# IPMC_MACP_-_2.net
KiCad netlist of a schematic drawn in Altium Designer
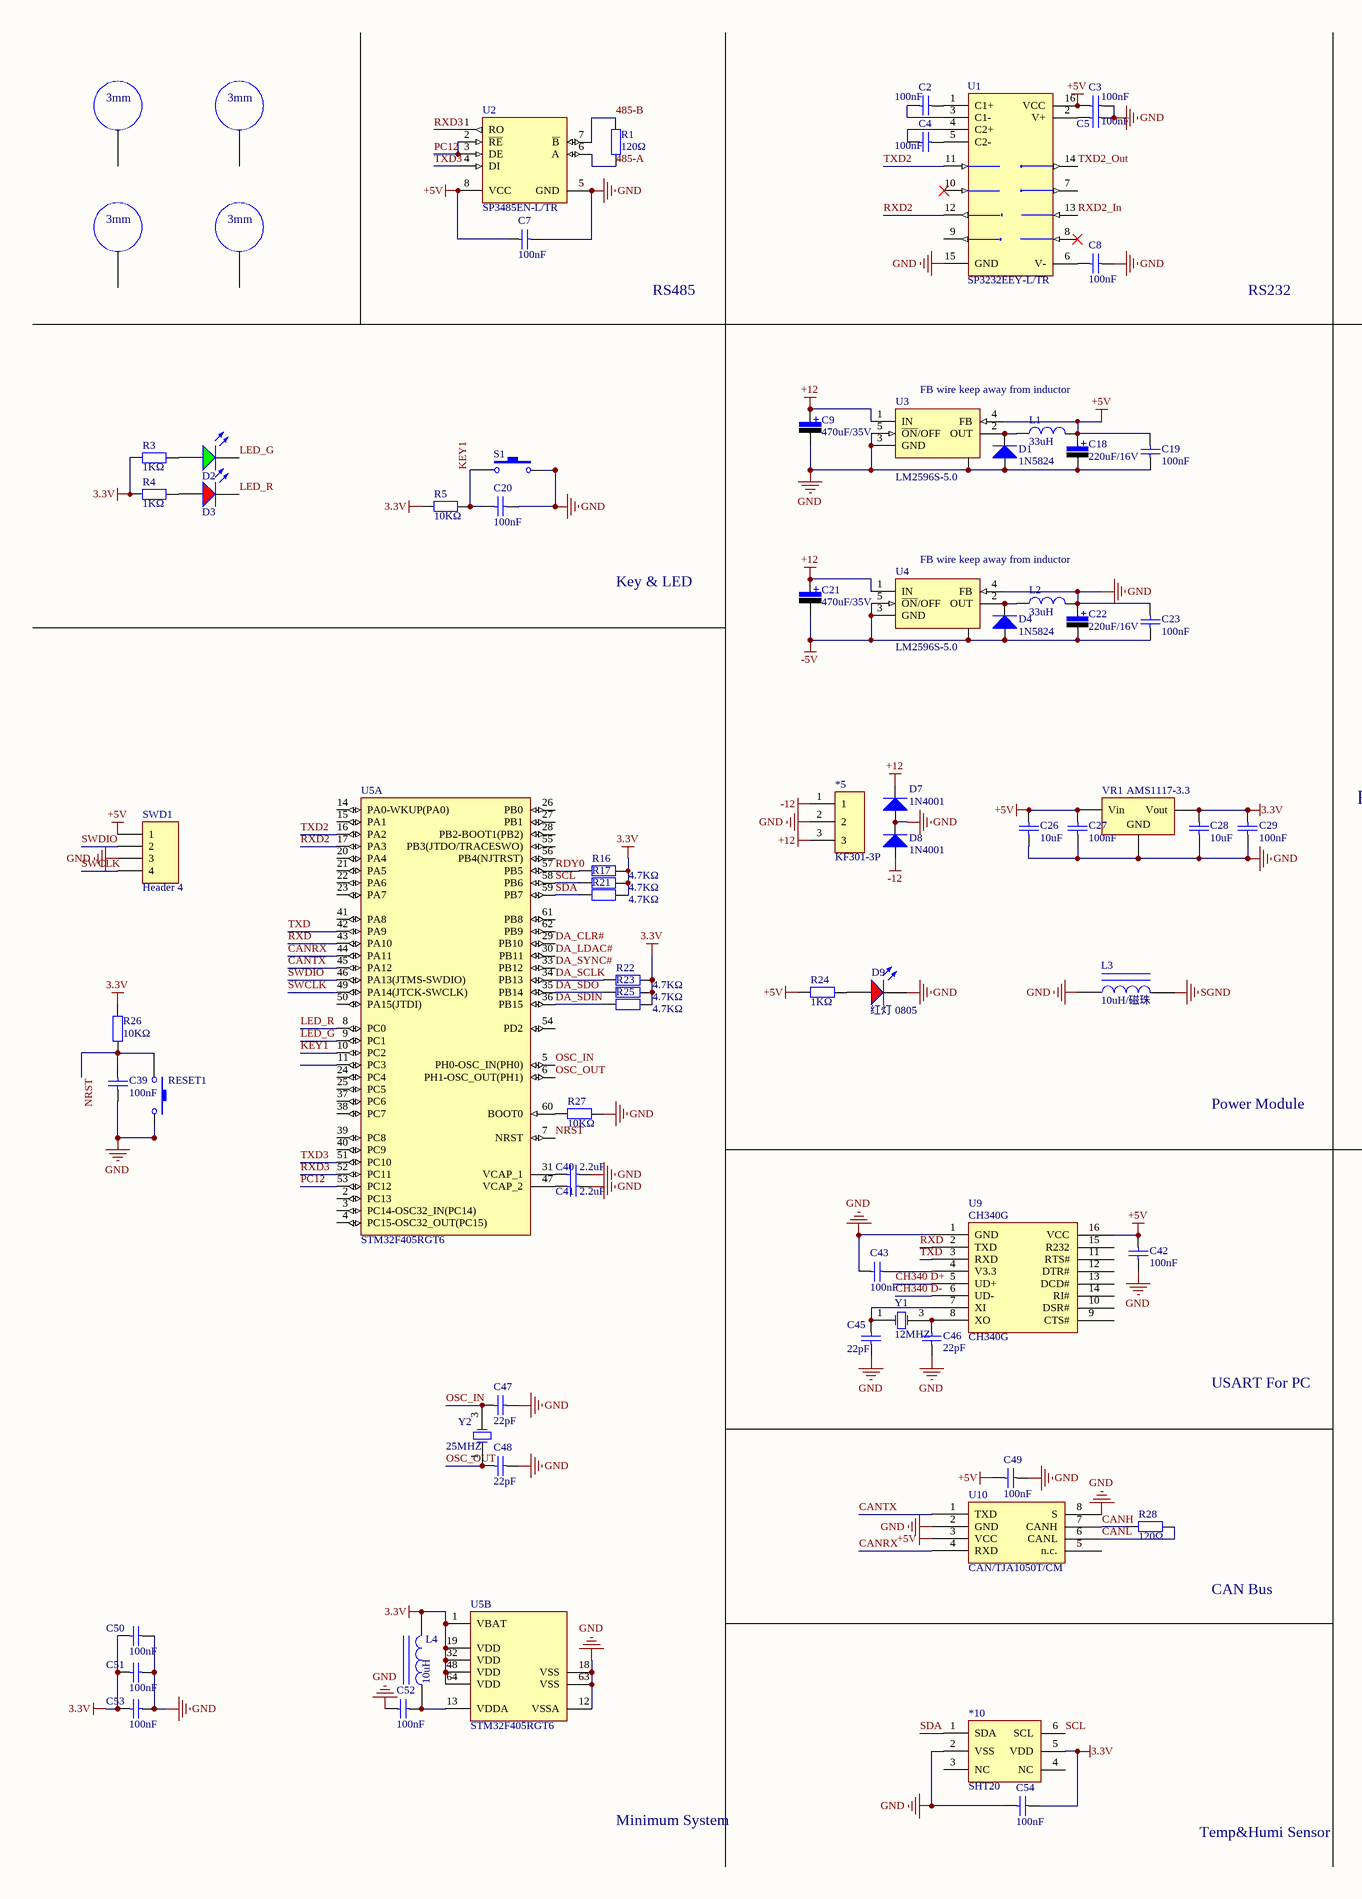
[diagram p0: IPMC_MACP - 完成2.SchDoc, left]
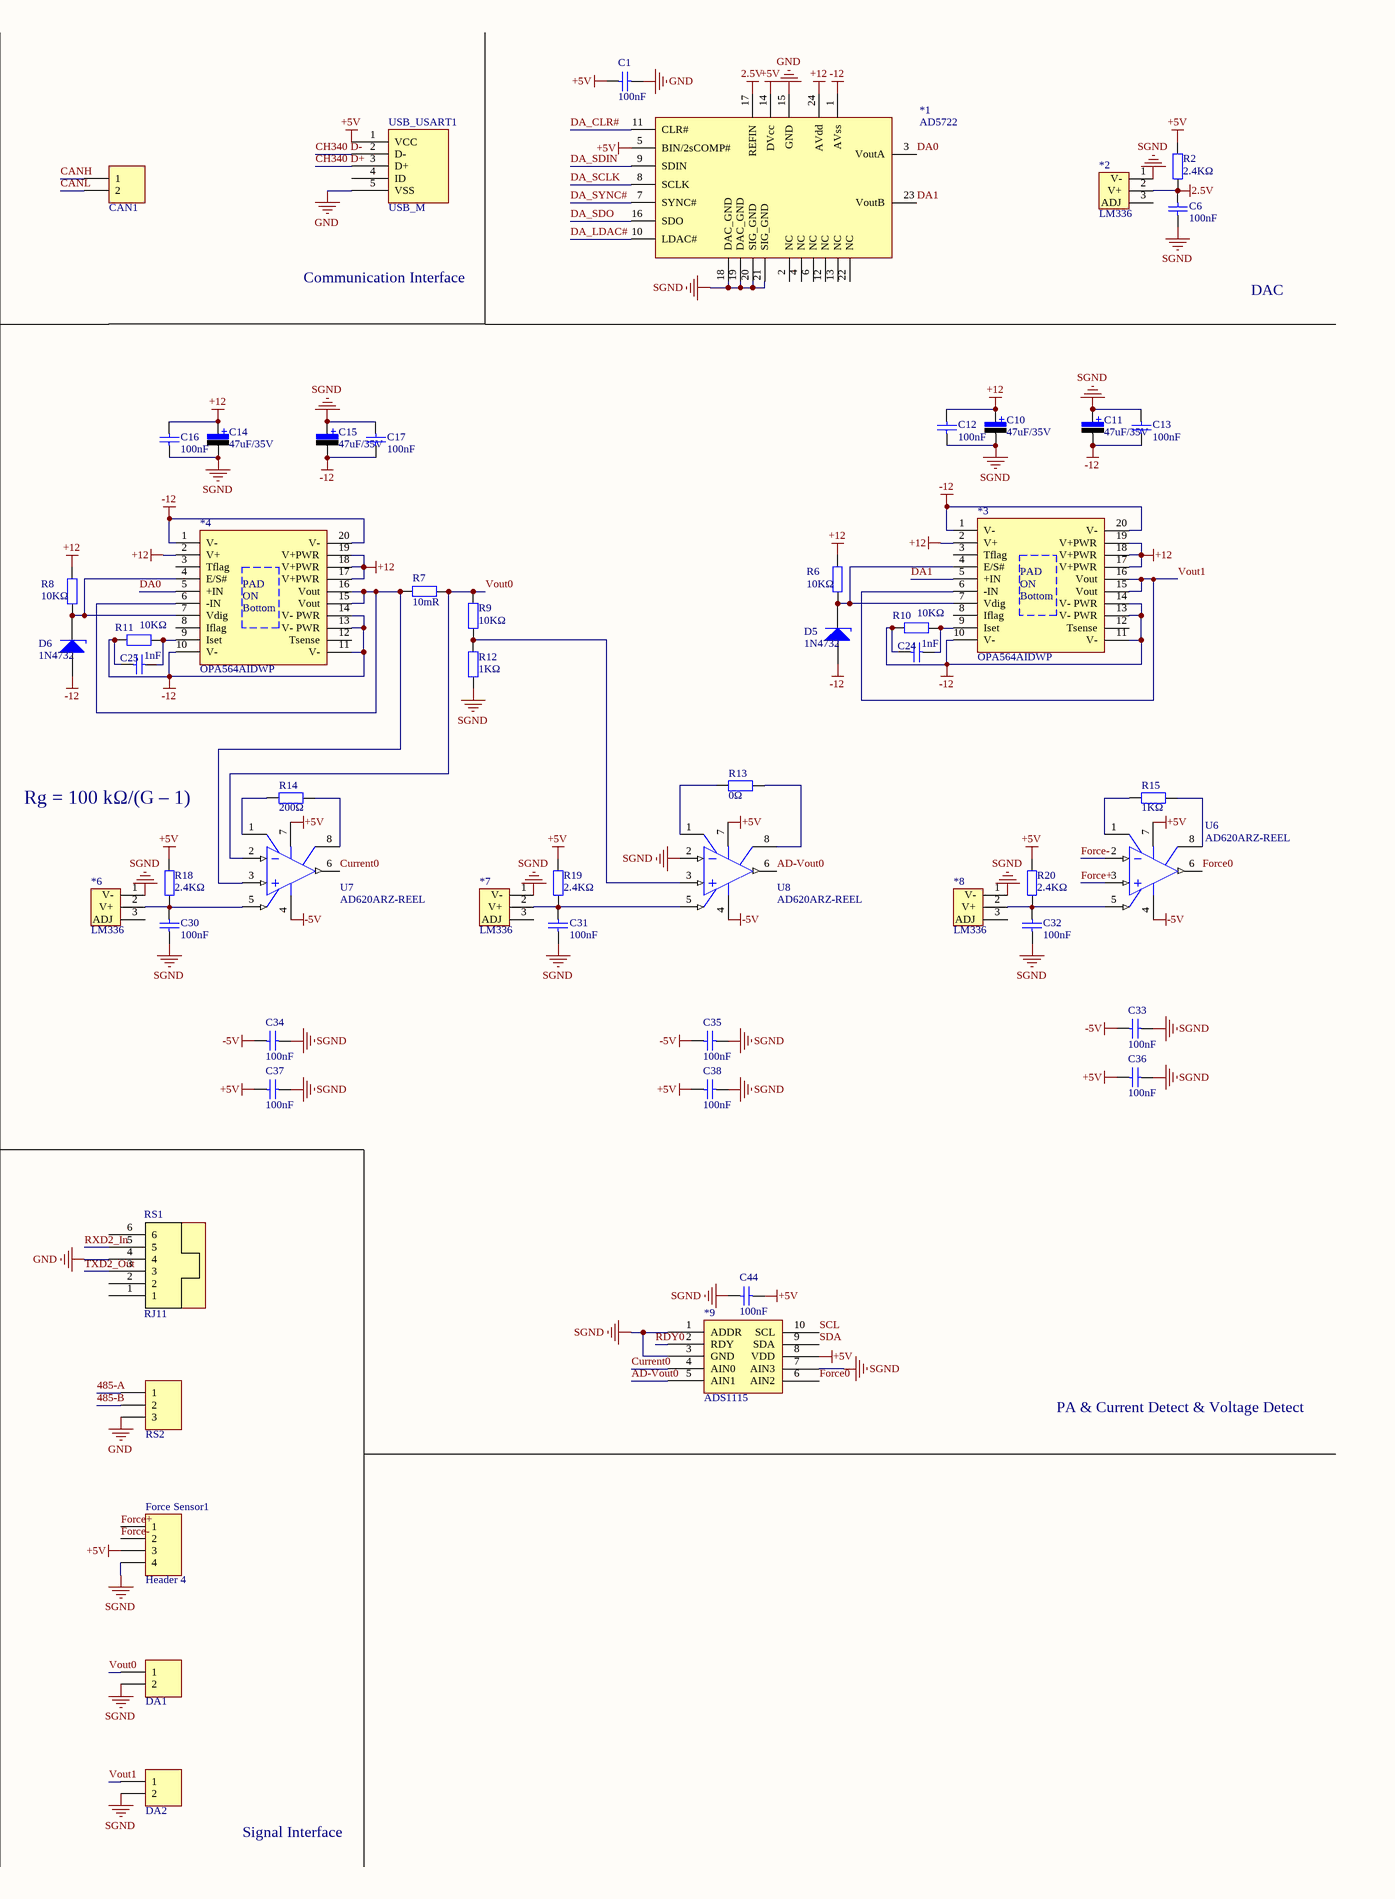
[diagram p1: IPMC_MACP - 完成2.SchDoc, right]

(export (version "E")
  (design (tool "Eeschema 10.0.6"))
  (components
    (comp (ref "*1")
      (value "AD5722")
      (footprint "TSSOP24P")
      (description "双极性DAC")
      (libsource (lib "fszhang") (part "AD5722"))
    )
    (comp (ref "*2")
      (value "LM336")
      (footprint "TO-92A")
      (description "基准电压芯片2.5/5V")
      (libsource (lib "fszhang") (part "LM336"))
    )
    (comp (ref "*3")
      (value "OPA564AIDWP")
      (footprint "HSOP20")
      (description "PAD on Bottom")
      (libsource (lib "fszhang") (part "OPA564AIDWP"))
    )
    (comp (ref "*4")
      (value "OPA564AIDWP")
      (footprint "HSOP20")
      (description "PAD on Bottom")
      (libsource (lib "fszhang") (part "OPA564AIDWP"))
    )
    (comp (ref "*5")
      (value "KF301-3P")
      (footprint "KF301-3P")
      (description "蓝色端子")
      (libsource (lib "fszhang") (part "KF301-3P"))
    )
    (comp (ref "*6")
      (value "LM336")
      (footprint "TO-92A")
      (description "基准电压芯片2.5/5V")
      (libsource (lib "fszhang") (part "LM336"))
    )
    (comp (ref "*7")
      (value "LM336")
      (footprint "TO-92A")
      (description "基准电压芯片2.5/5V")
      (libsource (lib "fszhang") (part "LM336"))
    )
    (comp (ref "*8")
      (value "LM336")
      (footprint "TO-92A")
      (description "基准电压芯片2.5/5V")
      (libsource (lib "fszhang") (part "LM336"))
    )
    (comp (ref "*9") (value "ADS1115") (footprint "MSOP-UN10_N") (libsource (lib "fszhang") (part "ADS1115")))
    (comp (ref "*10") (value "SHT20") (footprint "DFN6") (libsource (lib "fszhang") (part "SHT20")))
    (comp (ref "C1")
      (value "100nF")
      (footprint "0805_C")
      (description "贴片电容")
      (libsource (lib "Miscellaneous Devices LC") (part "0805 100nF(104) 10% 50V"))
    )
    (comp (ref "C2")
      (value "100nF")
      (footprint "0805_C")
      (description "贴片电容")
      (libsource (lib "Miscellaneous Devices LC") (part "0805 100nF(104) 10% 50V"))
    )
    (comp (ref "C3")
      (value "100nF")
      (footprint "0805_C")
      (description "贴片电容")
      (libsource (lib "Miscellaneous Devices LC") (part "0805 100nF(104) 10% 50V"))
    )
    (comp (ref "C4")
      (value "100nF")
      (footprint "0805_C")
      (description "贴片电容")
      (libsource (lib "Miscellaneous Devices LC") (part "0805 100nF(104) 10% 50V"))
    )
    (comp (ref "C5")
      (value "100nF")
      (footprint "0805_C")
      (description "贴片电容")
      (libsource (lib "Miscellaneous Devices LC") (part "0805 100nF(104) 10% 50V"))
    )
    (comp (ref "C6")
      (value "100nF")
      (footprint "0805_C")
      (description "贴片电容")
      (libsource (lib "Miscellaneous Devices LC") (part "0805 100nF(104) 10% 50V"))
    )
    (comp (ref "C7")
      (value "100nF")
      (footprint "0805_C")
      (description "贴片电容")
      (libsource (lib "Miscellaneous Devices LC") (part "0805 100nF(104) 10% 50V"))
    )
    (comp (ref "C8")
      (value "100nF")
      (footprint "0805_C")
      (description "贴片电容")
      (libsource (lib "Miscellaneous Devices LC") (part "0805 100nF(104) 10% 50V"))
    )
    (comp (ref "C9")
      (value "470uF/35V")
      (footprint "C-RB-S10")
      (description "极性电解电容")
      (fields (field (name "PUBLISHER") "Altium Limited"))
      (libsource (lib "fszhang") (part "Cap Pol"))
    )
    (comp (ref "C10")
      (value "47uF/35V")
      (footprint "C-RB-S6")
      (description "极性电解电容")
      (fields (field (name "PUBLISHER") "Altium Limited"))
      (libsource (lib "fszhang") (part "Cap Pol"))
    )
    (comp (ref "C11")
      (value "47uF/35V")
      (footprint "C-RB-S6")
      (description "极性电解电容")
      (fields (field (name "PUBLISHER") "Altium Limited"))
      (libsource (lib "fszhang") (part "Cap Pol"))
    )
    (comp (ref "C12")
      (value "100nF")
      (footprint "0805_C")
      (description "贴片电容")
      (libsource (lib "Miscellaneous Devices LC") (part "0805 100nF(104) 10% 50V"))
    )
    (comp (ref "C13")
      (value "100nF")
      (footprint "0805_C")
      (description "贴片电容")
      (libsource (lib "Miscellaneous Devices LC") (part "0805 100nF(104) 10% 50V"))
    )
    (comp (ref "C14")
      (value "47uF/35V")
      (footprint "C-RB-S6")
      (description "极性电解电容")
      (fields (field (name "PUBLISHER") "Altium Limited"))
      (libsource (lib "fszhang") (part "Cap Pol"))
    )
    (comp (ref "C15")
      (value "47uF/35V")
      (footprint "C-RB-S6")
      (description "极性电解电容")
      (fields (field (name "PUBLISHER") "Altium Limited"))
      (libsource (lib "fszhang") (part "Cap Pol"))
    )
    (comp (ref "C16")
      (value "100nF")
      (footprint "0805_C")
      (description "贴片电容")
      (libsource (lib "Miscellaneous Devices LC") (part "0805 100nF(104) 10% 50V"))
    )
    (comp (ref "C17")
      (value "100nF")
      (footprint "0805_C")
      (description "贴片电容")
      (libsource (lib "Miscellaneous Devices LC") (part "0805 100nF(104) 10% 50V"))
    )
    (comp (ref "C18")
      (value "220uF/16V")
      (footprint "C-RB-S6")
      (description "极性电解电容")
      (fields (field (name "PUBLISHER") "Altium Limited"))
      (libsource (lib "fszhang") (part "Cap Pol"))
    )
    (comp (ref "C19")
      (value "100nF")
      (footprint "0805_C")
      (description "贴片电容")
      (libsource (lib "Miscellaneous Devices LC") (part "0805 100nF(104) 10% 50V"))
    )
    (comp (ref "C20")
      (value "100nF")
      (footprint "0805_C")
      (description "贴片电容")
      (libsource (lib "Miscellaneous Devices LC") (part "0805 100nF(104) 10% 50V"))
    )
    (comp (ref "C21")
      (value "470uF/35V")
      (footprint "C-RB-S10")
      (description "极性电解电容")
      (fields (field (name "PUBLISHER") "Altium Limited"))
      (libsource (lib "fszhang") (part "Cap Pol"))
    )
    (comp (ref "C22")
      (value "220uF/16V")
      (footprint "C-RB-S6")
      (description "极性电解电容")
      (fields (field (name "PUBLISHER") "Altium Limited"))
      (libsource (lib "fszhang") (part "Cap Pol"))
    )
    (comp (ref "C23")
      (value "100nF")
      (footprint "0805_C")
      (description "贴片电容")
      (libsource (lib "Miscellaneous Devices LC") (part "0805 100nF(104) 10% 50V"))
    )
    (comp (ref "C24")
      (value "1nF")
      (footprint "0805_C")
      (description "贴片电容")
      (libsource (lib "Miscellaneous Devices LC") (part "0805 1nF (102) 10% 50V"))
    )
    (comp (ref "C25")
      (value "1nF")
      (footprint "0805_C")
      (description "贴片电容")
      (libsource (lib "Miscellaneous Devices LC") (part "0805 1nF (102) 10% 50V"))
    )
    (comp (ref "C26")
      (value "10uF")
      (footprint "0805_C")
      (description "贴片电容")
      (libsource (lib "Miscellaneous Devices LC") (part "0805 10uF (106) 10% 25V"))
    )
    (comp (ref "C27")
      (value "100nF")
      (footprint "0805_C")
      (description "贴片电容")
      (libsource (lib "Miscellaneous Devices LC") (part "0805 100nF(104) 10% 50V"))
    )
    (comp (ref "C28")
      (value "10uF")
      (footprint "0805_C")
      (description "贴片电容")
      (libsource (lib "Miscellaneous Devices LC") (part "0805 10uF (106) 10% 25V"))
    )
    (comp (ref "C29")
      (value "100nF")
      (footprint "0805_C")
      (description "贴片电容")
      (libsource (lib "Miscellaneous Devices LC") (part "0805 100nF(104) 10% 50V"))
    )
    (comp (ref "C30")
      (value "100nF")
      (footprint "0805_C")
      (description "贴片电容")
      (libsource (lib "Miscellaneous Devices LC") (part "0805 100nF(104) 10% 50V"))
    )
    (comp (ref "C31")
      (value "100nF")
      (footprint "0805_C")
      (description "贴片电容")
      (libsource (lib "Miscellaneous Devices LC") (part "0805 100nF(104) 10% 50V"))
    )
    (comp (ref "C32")
      (value "100nF")
      (footprint "0805_C")
      (description "贴片电容")
      (libsource (lib "Miscellaneous Devices LC") (part "0805 100nF(104) 10% 50V"))
    )
    (comp (ref "C33")
      (value "100nF")
      (footprint "0805_C")
      (description "贴片电容")
      (libsource (lib "Miscellaneous Devices LC") (part "0805 100nF(104) 10% 50V"))
    )
    (comp (ref "C34")
      (value "100nF")
      (footprint "0805_C")
      (description "贴片电容")
      (libsource (lib "Miscellaneous Devices LC") (part "0805 100nF(104) 10% 50V"))
    )
    (comp (ref "C35")
      (value "100nF")
      (footprint "0805_C")
      (description "贴片电容")
      (libsource (lib "Miscellaneous Devices LC") (part "0805 100nF(104) 10% 50V"))
    )
    (comp (ref "C36")
      (value "100nF")
      (footprint "0805_C")
      (description "贴片电容")
      (libsource (lib "Miscellaneous Devices LC") (part "0805 100nF(104) 10% 50V"))
    )
    (comp (ref "C37")
      (value "100nF")
      (footprint "0805_C")
      (description "贴片电容")
      (libsource (lib "Miscellaneous Devices LC") (part "0805 100nF(104) 10% 50V"))
    )
    (comp (ref "C38")
      (value "100nF")
      (footprint "0805_C")
      (description "贴片电容")
      (libsource (lib "Miscellaneous Devices LC") (part "0805 100nF(104) 10% 50V"))
    )
    (comp (ref "C39")
      (value "100nF")
      (footprint "0805_C")
      (description "贴片电容")
      (libsource (lib "Miscellaneous Devices LC") (part "0805 100nF(104) 10% 50V"))
    )
    (comp (ref "C40")
      (value "2.2uF")
      (footprint "0805_C")
      (description "贴片电容")
      (libsource (lib "Miscellaneous Devices LC") (part "0805 2.2uF (225) 20% 50V"))
    )
    (comp (ref "C41")
      (value "2.2uF")
      (footprint "0805_C")
      (description "贴片电容")
      (libsource (lib "Miscellaneous Devices LC") (part "0805 2.2uF (225) 20% 50V"))
    )
    (comp (ref "C42")
      (value "100nF")
      (footprint "0805_C")
      (description "贴片电容")
      (libsource (lib "Miscellaneous Devices LC") (part "0805 100nF(104) 10% 50V"))
    )
    (comp (ref "C43")
      (value "100nF")
      (footprint "0805_C")
      (description "贴片电容")
      (libsource (lib "Miscellaneous Devices LC") (part "0805 100nF(104) 10% 50V"))
    )
    (comp (ref "C44")
      (value "100nF")
      (footprint "0805_C")
      (description "贴片电容")
      (libsource (lib "Miscellaneous Devices LC") (part "0805 100nF(104) 10% 50V"))
    )
    (comp (ref "C45")
      (value "22pF")
      (footprint "0805_C")
      (description "贴片电容")
      (libsource (lib "Miscellaneous Devices LC") (part "0805 22pF (220) 5% 50V"))
    )
    (comp (ref "C46")
      (value "22pF")
      (footprint "0805_C")
      (description "贴片电容")
      (libsource (lib "Miscellaneous Devices LC") (part "0805 22pF (220) 5% 50V"))
    )
    (comp (ref "C47")
      (value "22pF")
      (footprint "0805_C")
      (description "贴片电容")
      (libsource (lib "Miscellaneous Devices LC") (part "0805 22pF (220) 5% 50V"))
    )
    (comp (ref "C48")
      (value "22pF")
      (footprint "0805_C")
      (description "贴片电容")
      (libsource (lib "Miscellaneous Devices LC") (part "0805 22pF (220) 5% 50V"))
    )
    (comp (ref "C49")
      (value "100nF")
      (footprint "0805_C")
      (description "贴片电容")
      (libsource (lib "Miscellaneous Devices LC") (part "0805 100nF(104) 10% 50V"))
    )
    (comp (ref "C50")
      (value "100nF")
      (footprint "0805_C")
      (description "贴片电容")
      (libsource (lib "Miscellaneous Devices LC") (part "0805 100nF(104) 10% 50V"))
    )
    (comp (ref "C51")
      (value "100nF")
      (footprint "0805_C")
      (description "贴片电容")
      (libsource (lib "Miscellaneous Devices LC") (part "0805 100nF(104) 10% 50V"))
    )
    (comp (ref "C52")
      (value "100nF")
      (footprint "0805_C")
      (description "贴片电容")
      (libsource (lib "Miscellaneous Devices LC") (part "0805 100nF(104) 10% 50V"))
    )
    (comp (ref "C53")
      (value "100nF")
      (footprint "0805_C")
      (description "贴片电容")
      (libsource (lib "Miscellaneous Devices LC") (part "0805 100nF(104) 10% 50V"))
    )
    (comp (ref "C54")
      (value "100nF")
      (footprint "0805_C")
      (description "贴片电容")
      (libsource (lib "Miscellaneous Devices LC") (part "0805 100nF(104) 10% 50V"))
    )
    (comp (ref "CAN1")
      (value "Header 2")
      (footprint "HDR2X1_B1")
      (description "接插件")
      (fields (field (name "PUBLISHER") "Altium Limited"))
      (libsource (lib "fszhang") (part "Header 2"))
    )
    (comp (ref "D1")
      (value "1N5824")
      (footprint "DIODE-SMA")
      (description "二极管")
      (fields (field (name "PUBLISHER") "Altium Limited"))
      (libsource (lib "fszhang") (part "Diode"))
    )
    (comp (ref "D2")
      (value "翠绿 0805")
      (footprint "0805_LED_S1")
      (description "发光二极管")
      (libsource (lib "Miscellaneous Devices LC") (part "0805 翠绿"))
    )
    (comp (ref "D3")
      (value "红灯 0805")
      (footprint "0805_LED_S1")
      (description "发光二极管")
      (libsource (lib "Miscellaneous Devices LC") (part "0805 红灯"))
    )
    (comp (ref "D4")
      (value "1N5824")
      (footprint "DIODE-SMA")
      (description "二极管")
      (fields (field (name "PUBLISHER") "Altium Limited"))
      (libsource (lib "fszhang") (part "Diode"))
    )
    (comp (ref "D5")
      (value "1N4732")
      (footprint "DIODE-1206")
      (description "稳压二极管")
      (fields (field (name "PUBLISHER") "Altium Limited"))
      (libsource (lib "fszhang") (part "Diode-Z"))
    )
    (comp (ref "D6")
      (value "1N4732")
      (footprint "DIODE-1206")
      (description "稳压二极管")
      (fields (field (name "PUBLISHER") "Altium Limited"))
      (libsource (lib "fszhang") (part "Diode-Z"))
    )
    (comp (ref "D7")
      (value "1N4001")
      (footprint "DIODE-SMA")
      (description "二极管")
      (fields (field (name "PUBLISHER") "Altium Limited"))
      (libsource (lib "fszhang") (part "Diode"))
    )
    (comp (ref "D8")
      (value "1N4001")
      (footprint "DIODE-SMA")
      (description "二极管")
      (fields (field (name "PUBLISHER") "Altium Limited"))
      (libsource (lib "fszhang") (part "Diode"))
    )
    (comp (ref "D9")
      (value "红灯 0805")
      (footprint "0805_LED_S1")
      (description "发光二极管")
      (libsource (lib "Miscellaneous Devices LC") (part "0805 红灯"))
    )
    (comp (ref "DA1")
      (value "Header 2")
      (footprint "HDR2X1_B1")
      (description "接插件")
      (fields (field (name "PUBLISHER") "Altium Limited"))
      (libsource (lib "fszhang") (part "Header 2"))
    )
    (comp (ref "DA2")
      (value "Header 2")
      (footprint "HDR2X1_B1")
      (description "接插件")
      (fields (field (name "PUBLISHER") "Altium Limited"))
      (libsource (lib "fszhang") (part "Header 2"))
    )
    (comp (ref "Force Sensor1")
      (value "Header 4")
      (footprint "fszhang:HDR4X1_B1")
      (description "Header, 4-Pin")
      (fields (field (name "PUBLISHER") "Altium Limited"))
      (libsource (lib "Miscellaneous Connectors") (part "Header 4"))
    )
    (comp (ref "L1")
      (value "33uH")
      (footprint "L-SMD-12")
      (description "电感")
      (fields (field (name "PUBLISHER") "Altium Limited"))
      (libsource (lib "fszhang") (part "Inductor"))
    )
    (comp (ref "L2")
      (value "33uH")
      (footprint "L-SMD-12")
      (description "电感")
      (fields (field (name "PUBLISHER") "Altium Limited"))
      (libsource (lib "fszhang") (part "Inductor"))
    )
    (comp (ref "L3")
      (value "10uH/磁珠")
      (footprint "0805_L")
      (description "贴片电感")
      (libsource (lib "Miscellaneous Devices LC") (part "0805 10uH 10%"))
    )
    (comp (ref "L4")
      (value "10uH")
      (footprint "0805_L")
      (description "贴片电感")
      (libsource (lib "Miscellaneous Devices LC") (part "0805 10uH 10%"))
    )
    (comp (ref "R1")
      (value "120Ω")
      (footprint "0805_R")
      (description "贴片电阻")
      (libsource (lib "Miscellaneous Devices LC") (part "0805 120Ω (1200) 1%"))
    )
    (comp (ref "R2")
      (value "2.4KΩ")
      (footprint "0805_R")
      (description "贴片电阻")
      (libsource (lib "Miscellaneous Devices LC") (part "0805 2.4KΩ (2401) 1%"))
    )
    (comp (ref "R3")
      (value "1KΩ")
      (footprint "0805_R")
      (description "贴片电阻")
      (libsource (lib "Miscellaneous Devices LC") (part "0805 1KΩ (1001) 1%"))
    )
    (comp (ref "R4")
      (value "1KΩ")
      (footprint "0805_R")
      (description "贴片电阻")
      (libsource (lib "Miscellaneous Devices LC") (part "0805 1KΩ (1001) 1%"))
    )
    (comp (ref "R5")
      (value "10KΩ")
      (footprint "0805_R")
      (description "贴片电阻")
      (libsource (lib "Miscellaneous Devices LC") (part "0805 10KΩ (1002) 1%"))
    )
    (comp (ref "R6")
      (value "10KΩ")
      (footprint "0805_R")
      (description "贴片电阻")
      (libsource (lib "") (part "0805 10KΩ (1002) 1%_2"))
    )
    (comp (ref "R7")
      (value "10mR")
      (footprint "2512")
      (description "贴片电阻")
      (fields (field (name "PUBLISHER") "Altium Limited"))
      (libsource (lib "fszhang") (part "Res1"))
    )
    (comp (ref "R8")
      (value "10KΩ")
      (footprint "0805_R")
      (description "贴片电阻")
      (libsource (lib "") (part "0805 10KΩ (1002) 1%_2"))
    )
    (comp (ref "R9")
      (value "10KΩ")
      (footprint "0805_R")
      (description "贴片电阻")
      (libsource (lib "Miscellaneous Devices LC") (part "0805 20KΩ (2002) 1%"))
    )
    (comp (ref "R10")
      (value "10KΩ")
      (footprint "0805_R")
      (description "贴片电阻")
      (libsource (lib "Miscellaneous Devices LC") (part "0805 10KΩ (1002) 1%"))
    )
    (comp (ref "R11")
      (value "10KΩ")
      (footprint "0805_R")
      (description "贴片电阻")
      (libsource (lib "Miscellaneous Devices LC") (part "0805 10KΩ (1002) 1%"))
    )
    (comp (ref "R12")
      (value "1KΩ")
      (footprint "0805_R")
      (description "贴片电阻")
      (libsource (lib "Miscellaneous Devices LC") (part "0805 20KΩ (2002) 1%"))
    )
    (comp (ref "R13")
      (value "0Ω")
      (footprint "0805_R")
      (description "贴片电阻")
      (libsource (lib "Miscellaneous Devices LC") (part "0805 0Ω (0R0) 1%"))
    )
    (comp (ref "R14")
      (value "200Ω")
      (footprint "0805_R")
      (description "贴片电阻")
      (libsource (lib "Miscellaneous Devices LC") (part "0805 200Ω (2000) 1%"))
    )
    (comp (ref "R15")
      (value "1KΩ")
      (footprint "0805_R")
      (description "贴片电阻")
      (libsource (lib "Miscellaneous Devices LC") (part "0805 1KΩ (1001) 1%"))
    )
    (comp (ref "R16")
      (value "4.7KΩ")
      (footprint "0805_R")
      (description "贴片电阻")
      (libsource (lib "Miscellaneous Devices LC") (part "0805 4.7KΩ (4701) 1%"))
    )
    (comp (ref "R17")
      (value "4.7KΩ")
      (footprint "0805_R")
      (description "贴片电阻")
      (libsource (lib "Miscellaneous Devices LC") (part "0805 4.7KΩ (4701) 1%"))
    )
    (comp (ref "R18")
      (value "2.4KΩ")
      (footprint "0805_R")
      (description "贴片电阻")
      (libsource (lib "Miscellaneous Devices LC") (part "0805 2.4KΩ (2401) 1%"))
    )
    (comp (ref "R19")
      (value "2.4KΩ")
      (footprint "0805_R")
      (description "贴片电阻")
      (libsource (lib "Miscellaneous Devices LC") (part "0805 2.4KΩ (2401) 1%"))
    )
    (comp (ref "R20")
      (value "2.4KΩ")
      (footprint "0805_R")
      (description "贴片电阻")
      (libsource (lib "Miscellaneous Devices LC") (part "0805 2.4KΩ (2401) 1%"))
    )
    (comp (ref "R21")
      (value "4.7KΩ")
      (footprint "0805_R")
      (description "贴片电阻")
      (libsource (lib "Miscellaneous Devices LC") (part "0805 4.7KΩ (4701) 1%"))
    )
    (comp (ref "R22")
      (value "4.7KΩ")
      (footprint "0805_R")
      (description "贴片电阻")
      (libsource (lib "Miscellaneous Devices LC") (part "0805 4.7KΩ (4701) 1%"))
    )
    (comp (ref "R23")
      (value "4.7KΩ")
      (footprint "0805_R")
      (description "贴片电阻")
      (libsource (lib "Miscellaneous Devices LC") (part "0805 4.7KΩ (4701) 1%"))
    )
    (comp (ref "R24")
      (value "1KΩ")
      (footprint "0805_R")
      (description "贴片电阻")
      (libsource (lib "Miscellaneous Devices LC") (part "0805 1KΩ (1001) 1%"))
    )
    (comp (ref "R25")
      (value "4.7KΩ")
      (footprint "0805_R")
      (description "贴片电阻")
      (libsource (lib "Miscellaneous Devices LC") (part "0805 4.7KΩ (4701) 1%"))
    )
    (comp (ref "R26")
      (value "10KΩ")
      (footprint "0805_R")
      (description "贴片电阻")
      (libsource (lib "") (part "0805 10KΩ (1002) 1%_1"))
    )
    (comp (ref "R27")
      (value "10KΩ")
      (footprint "0805_R")
      (description "贴片电阻")
      (libsource (lib "") (part "0805 10KΩ (1002) 1%_3"))
    )
    (comp (ref "R28")
      (value "120Ω")
      (footprint "0805_R")
      (description "贴片电阻")
      (libsource (lib "") (part "0805 120Ω (1200) 1%_1"))
    )
    (comp (ref "RESET1")
      (value "SW-PB")
      (footprint "SW_PB2_A1")
      (description "微动开关")
      (fields (field (name "PUBLISHER") "Altium Limited"))
      (libsource (lib "fszhang") (part "SW-PB"))
    )
    (comp (ref "RS1") (value "RJ11") (footprint "RJ6-RJ11") (libsource (lib "fszhang") (part "RJ11")))
    (comp (ref "RS2")
      (value "Header 3")
      (footprint "HDR3X1_B1")
      (description "接插件")
      (fields (field (name "PUBLISHER") "Altium Limited"))
      (libsource (lib "fszhang") (part "Header 3"))
    )
    (comp (ref "S1")
      (value "SW-PB")
      (footprint "SW_PB2_A1")
      (description "微动开关")
      (fields (field (name "PUBLISHER") "Altium Limited"))
      (libsource (lib "fszhang") (part "SW-PB"))
    )
    (comp (ref "SWD1")
      (value "Header 4")
      (footprint "HDR1X4")
      (description "Header, 4-Pin")
      (fields (field (name "PUBLISHER") "Altium Limited"))
      (libsource (lib "Miscellaneous Connectors") (part "Header 4"))
    )
    (comp (ref "T1") (value "M3铜柱螺丝孔") (footprint "螺丝孔-3mm") (libsource (lib "fszhang") (part "M3铜柱螺丝孔")))
    (comp (ref "T2") (value "M3铜柱螺丝孔") (footprint "螺丝孔-3mm") (libsource (lib "fszhang") (part "M3铜柱螺丝孔")))
    (comp (ref "T3") (value "M3铜柱螺丝孔") (footprint "螺丝孔-3mm") (libsource (lib "fszhang") (part "M3铜柱螺丝孔")))
    (comp (ref "T4") (value "M3铜柱螺丝孔") (footprint "螺丝孔-3mm") (libsource (lib "fszhang") (part "M3铜柱螺丝孔")))
    (comp (ref "U1")
      (value "SP3232EEY-L/TR")
      (footprint "TSSOP-16")
      (description "RS232")
      (libsource (lib "Miscellaneous Devices LC") (part "SP3232EEY-L/TR"))
    )
    (comp (ref "U2")
      (value "SP3485EN-L/TR")
      (footprint "SOIC-8_150mil")
      (description "RS-485/RS-422")
      (libsource (lib "Miscellaneous Devices LC") (part "SP3485EN-L/TR"))
    )
    (comp (ref "U3")
      (value "LM2596S-5.0")
      (footprint "TO-263-5")
      (description "5V稳压芯片")
      (fields (field (name "PUBLISHER") "Altium Limited"))
      (libsource (lib "fszhang") (part "LM2596S-5.0"))
    )
    (comp (ref "U4")
      (value "LM2596S-5.0")
      (footprint "TO-263-5")
      (description "5V稳压芯片")
      (fields (field (name "PUBLISHER") "Altium Limited"))
      (libsource (lib "fszhang") (part "LM2596S-5.0"))
    )
    (comp (ref "U5")
      (value "STM32F405RGT6")
      (footprint "STM-LQFP64_L")
      (fields (field (name "MANUFACTURER") "STMicroelectronics"))
      (libsource (lib "STMicroelectronics STM32 F4") (part "STM32F405RGT6"))
    )
    (comp (ref "U6")
      (value "AD620ARZ-REEL")
      (footprint "SOIC-8_150mil")
      (description "仪放")
      (libsource (lib "Miscellaneous Devices LC") (part "AD620ARZ-REEL"))
    )
    (comp (ref "U7")
      (value "AD620ARZ-REEL")
      (footprint "SOIC-8_150mil")
      (description "仪放")
      (libsource (lib "Miscellaneous Devices LC") (part "AD620ARZ-REEL"))
    )
    (comp (ref "U8")
      (value "AD620ARZ-REEL")
      (footprint "SOIC-8_150mil")
      (description "仪放")
      (libsource (lib "Miscellaneous Devices LC") (part "AD620ARZ-REEL"))
    )
    (comp (ref "U9")
      (value "CH340G")
      (footprint "SOIC-16_150mil")
      (description "USB")
      (libsource (lib "Miscellaneous Devices LC") (part "CH340G"))
    )
    (comp (ref "U10")
      (value "CAN/TJA1050T/CM")
      (footprint "SOIC-8_150mil")
      (description "CAN")
      (libsource (lib "Miscellaneous Devices LC") (part "CAN/TJA1050T/CM"))
    )
    (comp (ref "USB_USART1")
      (value "USB_M")
      (footprint "USB_MICRO")
      (description "MicroUSB接口")
      (libsource (lib "fszhang") (part "USB_M"))
    )
    (comp (ref "VR1")
      (value "AMS1117-3.3")
      (footprint "SOT-223")
      (description "低压差线性稳压(LDO)")
      (libsource (lib "Miscellaneous Devices LC") (part "SOT-223 AMS1117-3.3"))
    )
    (comp (ref "Y1")
      (value "12MHZ")
      (footprint "SMD-3225_4P")
      (description "贴片晶振")
      (libsource (lib "Miscellaneous Devices LC") (part "SMD-3225_4P  12MHZ 20PF 10PPM"))
    )
    (comp (ref "Y2")
      (value "25MHZ")
      (footprint "SMD-3225_4P")
      (description "贴片晶振")
      (libsource (lib "Miscellaneous Devices LC") (part "SMD-3225_4P  25MHZ 12PF 10PPM"))
    )
  )
  (nets
    (net (code "1") (name "+5V") (class "Default")
      (node (ref "*1") (pin "14") (pinfunction "DVcc_14") (pintype "passive"))
      (node (ref "*1") (pin "5") (pinfunction "BIN/2sCOMP#_5") (pintype "passive"))
      (node (ref "*9") (pin "8") (pinfunction "VDD_8") (pintype "passive"))
      (node (ref "C1") (pin "2") (pinfunction "2_2") (pintype "passive"))
      (node (ref "C18") (pin "1") (pinfunction "1_1") (pintype "passive"))
      (node (ref "C19") (pin "2") (pinfunction "2_2") (pintype "passive"))
      (node (ref "C26") (pin "2") (pinfunction "2_2") (pintype "passive"))
      (node (ref "C27") (pin "2") (pinfunction "2_2") (pintype "passive"))
      (node (ref "C3") (pin "1") (pinfunction "1_1") (pintype "passive"))
      (node (ref "C36") (pin "2") (pinfunction "2_2") (pintype "passive"))
      (node (ref "C37") (pin "2") (pinfunction "2_2") (pintype "passive"))
      (node (ref "C38") (pin "2") (pinfunction "2_2") (pintype "passive"))
      (node (ref "C42") (pin "2") (pinfunction "2_2") (pintype "passive"))
      (node (ref "C44") (pin "1") (pinfunction "1_1") (pintype "passive"))
      (node (ref "C49") (pin "2") (pinfunction "2_2") (pintype "passive"))
      (node (ref "C7") (pin "2") (pinfunction "2_2") (pintype "passive"))
      (node (ref "Force Sensor1") (pin "3") (pinfunction "3_3") (pintype "passive"))
      (node (ref "L1") (pin "2") (pinfunction "2_2") (pintype "passive"))
      (node (ref "R18") (pin "2") (pinfunction "2_2") (pintype "passive"))
      (node (ref "R19") (pin "2") (pinfunction "2_2") (pintype "passive"))
      (node (ref "R2") (pin "2") (pinfunction "2_2") (pintype "passive"))
      (node (ref "R20") (pin "2") (pinfunction "2_2") (pintype "passive"))
      (node (ref "R24") (pin "1") (pinfunction "1_1") (pintype "passive"))
      (node (ref "SWD1") (pin "1") (pinfunction "1_1") (pintype "passive"))
      (node (ref "U1") (pin "16") (pinfunction "VCC_16") (pintype "power_in"))
      (node (ref "U10") (pin "3") (pinfunction "VCC_3") (pintype "passive"))
      (node (ref "U2") (pin "8") (pinfunction "VCC_8") (pintype "power_in"))
      (node (ref "U3") (pin "4") (pinfunction "FB_4") (pintype "input"))
      (node (ref "U6") (pin "7") (pinfunction "V+_7") (pintype "power_in"))
      (node (ref "U7") (pin "7") (pinfunction "V+_7") (pintype "power_in"))
      (node (ref "U8") (pin "7") (pinfunction "V+_7") (pintype "power_in"))
      (node (ref "U9") (pin "16") (pinfunction "VCC_16") (pintype "passive"))
      (node (ref "USB_USART1") (pin "1") (pinfunction "VCC_1") (pintype "passive"))
      (node (ref "VR1") (pin "3") (pinfunction "Vin_3") (pintype "passive"))
    )
    (net (code "2") (name "+12") (class "Default")
      (node (ref "*1") (pin "24") (pinfunction "AVdd_24") (pintype "passive"))
      (node (ref "*3") (pin "17") (pinfunction "V+PWR_17") (pintype "passive"))
      (node (ref "*3") (pin "18") (pinfunction "V+PWR_18") (pintype "passive"))
      (node (ref "*3") (pin "19") (pinfunction "V+PWR_19") (pintype "passive"))
      (node (ref "*3") (pin "2") (pinfunction "V+_2") (pintype "passive"))
      (node (ref "*4") (pin "17") (pinfunction "V+PWR_17") (pintype "passive"))
      (node (ref "*4") (pin "18") (pinfunction "V+PWR_18") (pintype "passive"))
      (node (ref "*4") (pin "19") (pinfunction "V+PWR_19") (pintype "passive"))
      (node (ref "*4") (pin "2") (pinfunction "V+_2") (pintype "passive"))
      (node (ref "*5") (pin "3") (pinfunction "3_3") (pintype "passive"))
      (node (ref "C10") (pin "1") (pinfunction "1_1") (pintype "passive"))
      (node (ref "C12") (pin "2") (pinfunction "2_2") (pintype "passive"))
      (node (ref "C14") (pin "1") (pinfunction "1_1") (pintype "passive"))
      (node (ref "C16") (pin "2") (pinfunction "2_2") (pintype "passive"))
      (node (ref "C21") (pin "1") (pinfunction "1_1") (pintype "passive"))
      (node (ref "C9") (pin "1") (pinfunction "1_1") (pintype "passive"))
      (node (ref "D7") (pin "2") (pinfunction "K_2") (pintype "passive"))
      (node (ref "R6") (pin "2") (pinfunction "2_2") (pintype "passive"))
      (node (ref "R8") (pin "2") (pinfunction "2_2") (pintype "passive"))
      (node (ref "U3") (pin "1") (pinfunction "IN_1") (pintype "power_in"))
      (node (ref "U4") (pin "1") (pinfunction "IN_1") (pintype "power_in"))
    )
    (net (code "3") (name "-5V") (class "Default")
      (node (ref "C21") (pin "2") (pinfunction "2_2") (pintype "passive"))
      (node (ref "C22") (pin "2") (pinfunction "2_2") (pintype "passive"))
      (node (ref "C23") (pin "1") (pinfunction "1_1") (pintype "passive"))
      (node (ref "C33") (pin "2") (pinfunction "2_2") (pintype "passive"))
      (node (ref "C34") (pin "2") (pinfunction "2_2") (pintype "passive"))
      (node (ref "C35") (pin "2") (pinfunction "2_2") (pintype "passive"))
      (node (ref "D4") (pin "1") (pinfunction "A_1") (pintype "passive"))
      (node (ref "U4") (pin "3") (pinfunction "GND_3") (pintype "power_in"))
      (node (ref "U4") (pin "5") (pinfunction "~{ON}/OFF_5") (pintype "input"))
      (node (ref "U4") (pin "6") (pinfunction "6_6") (pintype "power_in"))
      (node (ref "U6") (pin "4") (pinfunction "V-_4") (pintype "power_in"))
      (node (ref "U7") (pin "4") (pinfunction "V-_4") (pintype "power_in"))
      (node (ref "U8") (pin "4") (pinfunction "V-_4") (pintype "power_in"))
    )
    (net (code "4") (name "-12") (class "Default")
      (node (ref "*1") (pin "1") (pinfunction "AVss_1") (pintype "passive"))
      (node (ref "*3") (pin "1") (pinfunction "V-_1") (pintype "passive"))
      (node (ref "*3") (pin "10") (pinfunction "V-_10") (pintype "passive"))
      (node (ref "*3") (pin "11") (pinfunction "V-_11") (pintype "passive"))
      (node (ref "*3") (pin "13") (pinfunction "V-_PWR_13") (pintype "passive"))
      (node (ref "*3") (pin "14") (pinfunction "V-_PWR_14") (pintype "passive"))
      (node (ref "*3") (pin "20") (pinfunction "V-_20") (pintype "passive"))
      (node (ref "*4") (pin "1") (pinfunction "V-_1") (pintype "passive"))
      (node (ref "*4") (pin "10") (pinfunction "V-_10") (pintype "passive"))
      (node (ref "*4") (pin "11") (pinfunction "V-_11") (pintype "passive"))
      (node (ref "*4") (pin "13") (pinfunction "V-_PWR_13") (pintype "passive"))
      (node (ref "*4") (pin "14") (pinfunction "V-_PWR_14") (pintype "passive"))
      (node (ref "*4") (pin "20") (pinfunction "V-_20") (pintype "passive"))
      (node (ref "*5") (pin "1") (pinfunction "1_1") (pintype "passive"))
      (node (ref "C11") (pin "2") (pinfunction "2_2") (pintype "passive"))
      (node (ref "C13") (pin "2") (pinfunction "2_2") (pintype "passive"))
      (node (ref "C15") (pin "2") (pinfunction "2_2") (pintype "passive"))
      (node (ref "C17") (pin "2") (pinfunction "2_2") (pintype "passive"))
      (node (ref "C24") (pin "1") (pinfunction "1_1") (pintype "passive"))
      (node (ref "C25") (pin "1") (pinfunction "1_1") (pintype "passive"))
      (node (ref "D5") (pin "1") (pinfunction "A_1") (pintype "passive"))
      (node (ref "D6") (pin "1") (pinfunction "A_1") (pintype "passive"))
      (node (ref "D8") (pin "1") (pinfunction "A_1") (pintype "passive"))
      (node (ref "R10") (pin "1") (pinfunction "1_1") (pintype "passive"))
      (node (ref "R11") (pin "1") (pinfunction "1_1") (pintype "passive"))
    )
    (net (code "5") (name "/485-A") (class "Default")
      (node (ref "R1") (pin "1") (pinfunction "1_1") (pintype "passive"))
      (node (ref "RS2") (pin "1") (pinfunction "1_1") (pintype "passive"))
      (node (ref "U2") (pin "6") (pinfunction "A_6") (pintype "bidirectional"))
    )
    (net (code "6") (name "/485-B") (class "Default")
      (node (ref "R1") (pin "2") (pinfunction "2_2") (pintype "passive"))
      (node (ref "RS2") (pin "2") (pinfunction "2_2") (pintype "passive"))
      (node (ref "U2") (pin "7") (pinfunction "~{B}_7") (pintype "bidirectional"))
    )
    (net (code "7") (name "/AD-Vout0") (class "Default")
      (node (ref "*9") (pin "5") (pinfunction "AIN1_5") (pintype "passive"))
      (node (ref "U8") (pin "6") (pinfunction "OUT_6") (pintype "output"))
    )
    (net (code "8") (name "/CANH") (class "Default")
      (node (ref "CAN1") (pin "1") (pinfunction "1_1") (pintype "passive"))
      (node (ref "R28") (pin "1") (pinfunction "1_1") (pintype "passive"))
      (node (ref "U10") (pin "7") (pinfunction "CANH_7") (pintype "passive"))
    )
    (net (code "9") (name "/CANL") (class "Default")
      (node (ref "CAN1") (pin "2") (pinfunction "2_2") (pintype "passive"))
      (node (ref "R28") (pin "2") (pinfunction "2_2") (pintype "passive"))
      (node (ref "U10") (pin "6") (pinfunction "CANL_6") (pintype "passive"))
    )
    (net (code "10") (name "/CANRX") (class "Default")
      (node (ref "U10") (pin "4") (pinfunction "RXD_4") (pintype "passive"))
      (node (ref "U5") (pin "44") (pinfunction "PA11_44") (pintype "bidirectional"))
    )
    (net (code "11") (name "/CANTX") (class "Default")
      (node (ref "U10") (pin "1") (pinfunction "TXD_1") (pintype "passive"))
      (node (ref "U5") (pin "45") (pinfunction "PA12_45") (pintype "bidirectional"))
    )
    (net (code "12") (name "/CH340 D+") (class "Default")
      (node (ref "U9") (pin "5") (pinfunction "UD+_5") (pintype "passive"))
      (node (ref "USB_USART1") (pin "3") (pinfunction "D+_3") (pintype "passive"))
    )
    (net (code "13") (name "/CH340 D-") (class "Default")
      (node (ref "U9") (pin "6") (pinfunction "UD-_6") (pintype "passive"))
      (node (ref "USB_USART1") (pin "2") (pinfunction "D-_2") (pintype "passive"))
    )
    (net (code "14") (name "/Current0") (class "Default")
      (node (ref "*9") (pin "4") (pinfunction "AIN0_4") (pintype "passive"))
      (node (ref "U7") (pin "6") (pinfunction "OUT_6") (pintype "output"))
    )
    (net (code "15") (name "/DA0") (class "Default")
      (node (ref "*1") (pin "3") (pinfunction "VoutA_3") (pintype "passive"))
      (node (ref "*4") (pin "5") (pinfunction "+IN_5") (pintype "passive"))
    )
    (net (code "16") (name "/DA1") (class "Default")
      (node (ref "*1") (pin "23") (pinfunction "VoutB_23") (pintype "passive"))
      (node (ref "*3") (pin "5") (pinfunction "+IN_5") (pintype "passive"))
    )
    (net (code "17") (name "/DA_CLR#") (class "Default")
      (node (ref "*1") (pin "11") (pinfunction "CLR#_11") (pintype "passive"))
      (node (ref "U5") (pin "29") (pinfunction "PB10_29") (pintype "bidirectional"))
    )
    (net (code "18") (name "/DA_LDAC#") (class "Default")
      (node (ref "*1") (pin "10") (pinfunction "LDAC#_10") (pintype "passive"))
      (node (ref "U5") (pin "30") (pinfunction "PB11_30") (pintype "bidirectional"))
    )
    (net (code "19") (name "/DA_SCLK") (class "Default")
      (node (ref "*1") (pin "8") (pinfunction "SCLK_8") (pintype "passive"))
      (node (ref "R22") (pin "1") (pinfunction "1_1") (pintype "passive"))
      (node (ref "U5") (pin "34") (pinfunction "PB13_34") (pintype "bidirectional"))
    )
    (net (code "20") (name "/DA_SDIN") (class "Default")
      (node (ref "*1") (pin "9") (pinfunction "SDIN_9") (pintype "passive"))
      (node (ref "R25") (pin "1") (pinfunction "1_1") (pintype "passive"))
      (node (ref "U5") (pin "36") (pinfunction "PB15_36") (pintype "bidirectional"))
    )
    (net (code "21") (name "/DA_SDO") (class "Default")
      (node (ref "*1") (pin "16") (pinfunction "SDO_16") (pintype "passive"))
      (node (ref "R23") (pin "1") (pinfunction "1_1") (pintype "passive"))
      (node (ref "U5") (pin "35") (pinfunction "PB14_35") (pintype "bidirectional"))
    )
    (net (code "22") (name "/DA_SYNC#") (class "Default")
      (node (ref "*1") (pin "7") (pinfunction "SYNC#_7") (pintype "passive"))
      (node (ref "U5") (pin "33") (pinfunction "PB12_33") (pintype "bidirectional"))
    )
    (net (code "23") (name "/Force+") (class "Default")
      (node (ref "Force Sensor1") (pin "1") (pinfunction "1_1") (pintype "passive"))
      (node (ref "U6") (pin "3") (pinfunction "+IN_3") (pintype "input"))
    )
    (net (code "24") (name "/Force-") (class "Default")
      (node (ref "Force Sensor1") (pin "2") (pinfunction "2_2") (pintype "passive"))
      (node (ref "U6") (pin "2") (pinfunction "-IN_2") (pintype "input"))
    )
    (net (code "25") (name "/Force0") (class "Default")
      (node (ref "*9") (pin "6") (pinfunction "AIN2_6") (pintype "passive"))
      (node (ref "U6") (pin "6") (pinfunction "OUT_6") (pintype "output"))
    )
    (net (code "26") (name "/KEY1") (class "Default")
      (node (ref "C20") (pin "1") (pinfunction "1_1") (pintype "passive"))
      (node (ref "R5") (pin "2") (pinfunction "2_2") (pintype "passive"))
      (node (ref "S1") (pin "1") (pinfunction "1_1") (pintype "passive"))
      (node (ref "U5") (pin "10") (pinfunction "PC2_10") (pintype "bidirectional"))
    )
    (net (code "27") (name "/LED_G") (class "Default")
      (node (ref "D2") (pin "K") (pinfunction "K_K") (pintype "passive"))
      (node (ref "U5") (pin "9") (pinfunction "PC1_9") (pintype "bidirectional"))
    )
    (net (code "28") (name "/LED_R") (class "Default")
      (node (ref "D3") (pin "K") (pinfunction "K_K") (pintype "passive"))
      (node (ref "U5") (pin "8") (pinfunction "PC0_8") (pintype "bidirectional"))
    )
    (net (code "29") (name "/NRST") (class "Default")
      (node (ref "C39") (pin "1") (pinfunction "1_1") (pintype "passive"))
      (node (ref "R26") (pin "2") (pinfunction "2_2") (pintype "passive"))
      (node (ref "RESET1") (pin "1") (pinfunction "1_1") (pintype "passive"))
      (node (ref "U5") (pin "7") (pinfunction "NRST_7") (pintype "bidirectional"))
    )
    (net (code "30") (name "/OSC_IN") (class "Default")
      (node (ref "C47") (pin "2") (pinfunction "2_2") (pintype "passive"))
      (node (ref "U5") (pin "5") (pinfunction "PH0-OSC_IN(PH0)_5") (pintype "bidirectional"))
      (node (ref "Y2") (pin "3") (pinfunction "OSC2_3") (pintype "passive"))
    )
    (net (code "31") (name "/OSC_OUT") (class "Default")
      (node (ref "C48") (pin "2") (pinfunction "2_2") (pintype "passive"))
      (node (ref "U5") (pin "6") (pinfunction "PH1-OSC_OUT(PH1)_6") (pintype "bidirectional"))
      (node (ref "Y2") (pin "1") (pinfunction "OSC1_1") (pintype "passive"))
    )
    (net (code "32") (name "/PC12") (class "Default")
      (node (ref "U2") (pin "2") (pinfunction "~{RE}_2") (pintype "input"))
      (node (ref "U2") (pin "3") (pinfunction "DE_3") (pintype "input"))
      (node (ref "U5") (pin "53") (pinfunction "PC12_53") (pintype "bidirectional"))
    )
    (net (code "33") (name "/RDY0") (class "Default")
      (node (ref "*9") (pin "2") (pinfunction "RDY_2") (pintype "passive"))
      (node (ref "R16") (pin "1") (pinfunction "1_1") (pintype "passive"))
      (node (ref "U5") (pin "57") (pinfunction "PB5_57") (pintype "bidirectional"))
    )
    (net (code "34") (name "/RXD") (class "Default")
      (node (ref "U5") (pin "43") (pinfunction "PA10_43") (pintype "bidirectional"))
      (node (ref "U9") (pin "2") (pinfunction "TXD_2") (pintype "passive"))
    )
    (net (code "35") (name "/RXD2") (class "Default")
      (node (ref "U1") (pin "12") (pinfunction "R1OUT_12") (pintype "output"))
      (node (ref "U5") (pin "17") (pinfunction "PA3_17") (pintype "bidirectional"))
    )
    (net (code "36") (name "/RXD2_In") (class "Default")
      (node (ref "RS1") (pin "5") (pinfunction "5_5") (pintype "passive"))
      (node (ref "U1") (pin "13") (pinfunction "R1IN_13") (pintype "input"))
    )
    (net (code "37") (name "/RXD3") (class "Default")
      (node (ref "U2") (pin "1") (pinfunction "RO_1") (pintype "output"))
      (node (ref "U5") (pin "52") (pinfunction "PC11_52") (pintype "bidirectional"))
    )
    (net (code "38") (name "/SCL") (class "Default")
      (node (ref "*10") (pin "6") (pinfunction "SCL_6") (pintype "passive"))
      (node (ref "*9") (pin "10") (pinfunction "SCL_10") (pintype "passive"))
      (node (ref "R17") (pin "1") (pinfunction "1_1") (pintype "passive"))
      (node (ref "U5") (pin "58") (pinfunction "PB6_58") (pintype "bidirectional"))
    )
    (net (code "39") (name "/SDA") (class "Default")
      (node (ref "*10") (pin "1") (pinfunction "SDA_1") (pintype "passive"))
      (node (ref "*9") (pin "9") (pinfunction "SDA_9") (pintype "passive"))
      (node (ref "R21") (pin "1") (pinfunction "1_1") (pintype "passive"))
      (node (ref "U5") (pin "59") (pinfunction "PB7_59") (pintype "bidirectional"))
    )
    (net (code "40") (name "/SWCLK") (class "Default")
      (node (ref "SWD1") (pin "4") (pinfunction "4_4") (pintype "passive"))
      (node (ref "U5") (pin "49") (pinfunction "PA14(JTCK-SWCLK)_49") (pintype "bidirectional"))
    )
    (net (code "41") (name "/SWDIO") (class "Default")
      (node (ref "SWD1") (pin "2") (pinfunction "2_2") (pintype "passive"))
      (node (ref "U5") (pin "46") (pinfunction "PA13(JTMS-SWDIO)_46") (pintype "bidirectional"))
    )
    (net (code "42") (name "/TXD") (class "Default")
      (node (ref "U5") (pin "42") (pinfunction "PA9_42") (pintype "bidirectional"))
      (node (ref "U9") (pin "3") (pinfunction "RXD_3") (pintype "passive"))
    )
    (net (code "43") (name "/TXD2") (class "Default")
      (node (ref "U1") (pin "11") (pinfunction "T1IN_11") (pintype "input"))
      (node (ref "U5") (pin "16") (pinfunction "PA2_16") (pintype "bidirectional"))
    )
    (net (code "44") (name "/TXD2_Out") (class "Default")
      (node (ref "RS1") (pin "3") (pinfunction "3_3") (pintype "passive"))
      (node (ref "U1") (pin "14") (pinfunction "T1OUT_14") (pintype "output"))
    )
    (net (code "45") (name "/TXD3") (class "Default")
      (node (ref "U2") (pin "4") (pinfunction "DI_4") (pintype "input"))
      (node (ref "U5") (pin "51") (pinfunction "PC10_51") (pintype "bidirectional"))
    )
    (net (code "46") (name "/Vout0") (class "Default")
      (node (ref "DA1") (pin "1") (pinfunction "1_1") (pintype "passive"))
      (node (ref "R7") (pin "2") (pinfunction "2_2") (pintype "passive"))
      (node (ref "R9") (pin "1") (pinfunction "1_1") (pintype "passive"))
      (node (ref "U7") (pin "2") (pinfunction "-IN_2") (pintype "input"))
    )
    (net (code "47") (name "/Vout1") (class "Default")
      (node (ref "*3") (pin "15") (pinfunction "Vout_15") (pintype "passive"))
      (node (ref "*3") (pin "16") (pinfunction "Vout_16") (pintype "passive"))
      (node (ref "*3") (pin "6") (pinfunction "-IN_6") (pintype "passive"))
      (node (ref "DA2") (pin "1") (pinfunction "1_1") (pintype "passive"))
    )
    (net (code "48") (name "2.5V") (class "Default")
      (node (ref "*1") (pin "17") (pinfunction "REFIN_17") (pintype "passive"))
      (node (ref "*2") (pin "2") (pinfunction "V+_2") (pintype "passive"))
      (node (ref "C6") (pin "2") (pinfunction "2_2") (pintype "passive"))
      (node (ref "R2") (pin "1") (pinfunction "1_1") (pintype "passive"))
    )
    (net (code "49") (name "3.3V") (class "Default")
      (node (ref "*10") (pin "5") (pinfunction "VDD_5") (pintype "passive"))
      (node (ref "C28") (pin "2") (pinfunction "2_2") (pintype "passive"))
      (node (ref "C29") (pin "2") (pinfunction "2_2") (pintype "passive"))
      (node (ref "C50") (pin "1") (pinfunction "1_1") (pintype "passive"))
      (node (ref "C51") (pin "1") (pinfunction "1_1") (pintype "passive"))
      (node (ref "C53") (pin "1") (pinfunction "1_1") (pintype "passive"))
      (node (ref "C54") (pin "1") (pinfunction "1_1") (pintype "passive"))
      (node (ref "L4") (pin "2") (pinfunction "2_2") (pintype "passive"))
      (node (ref "R16") (pin "2") (pinfunction "2_2") (pintype "passive"))
      (node (ref "R17") (pin "2") (pinfunction "2_2") (pintype "passive"))
      (node (ref "R21") (pin "2") (pinfunction "2_2") (pintype "passive"))
      (node (ref "R22") (pin "2") (pinfunction "2_2") (pintype "passive"))
      (node (ref "R23") (pin "2") (pinfunction "2_2") (pintype "passive"))
      (node (ref "R25") (pin "2") (pinfunction "2_2") (pintype "passive"))
      (node (ref "R26") (pin "1") (pinfunction "1_1") (pintype "passive"))
      (node (ref "R3") (pin "1") (pinfunction "1_1") (pintype "passive"))
      (node (ref "R4") (pin "1") (pinfunction "1_1") (pintype "passive"))
      (node (ref "R5") (pin "1") (pinfunction "1_1") (pintype "passive"))
      (node (ref "U5") (pin "1") (pinfunction "VBAT_1") (pintype "power_in"))
      (node (ref "U5") (pin "19") (pinfunction "VDD_19") (pintype "power_in"))
      (node (ref "U5") (pin "32") (pinfunction "VDD_32") (pintype "power_in"))
      (node (ref "U5") (pin "48") (pinfunction "VDD_48") (pintype "power_in"))
      (node (ref "U5") (pin "64") (pinfunction "VDD_64") (pintype "power_in"))
      (node (ref "VR1") (pin "2") (pinfunction "Vout_2") (pintype "passive"))
    )
    (net (code "50") (name "GND") (class "Default")
      (node (ref "*1") (pin "15") (pinfunction "GND_15") (pintype "passive"))
      (node (ref "*10") (pin "2") (pinfunction "VSS_2") (pintype "passive"))
      (node (ref "*5") (pin "2") (pinfunction "2_2") (pintype "passive"))
      (node (ref "C1") (pin "1") (pinfunction "1_1") (pintype "passive"))
      (node (ref "C18") (pin "2") (pinfunction "2_2") (pintype "passive"))
      (node (ref "C19") (pin "1") (pinfunction "1_1") (pintype "passive"))
      (node (ref "C20") (pin "2") (pinfunction "2_2") (pintype "passive"))
      (node (ref "C22") (pin "1") (pinfunction "1_1") (pintype "passive"))
      (node (ref "C23") (pin "2") (pinfunction "2_2") (pintype "passive"))
      (node (ref "C26") (pin "1") (pinfunction "1_1") (pintype "passive"))
      (node (ref "C27") (pin "1") (pinfunction "1_1") (pintype "passive"))
      (node (ref "C28") (pin "1") (pinfunction "1_1") (pintype "passive"))
      (node (ref "C29") (pin "1") (pinfunction "1_1") (pintype "passive"))
      (node (ref "C3") (pin "2") (pinfunction "2_2") (pintype "passive"))
      (node (ref "C39") (pin "2") (pinfunction "2_2") (pintype "passive"))
      (node (ref "C40") (pin "2") (pinfunction "2_2") (pintype "passive"))
      (node (ref "C41") (pin "2") (pinfunction "2_2") (pintype "passive"))
      (node (ref "C42") (pin "1") (pinfunction "1_1") (pintype "passive"))
      (node (ref "C43") (pin "2") (pinfunction "2_2") (pintype "passive"))
      (node (ref "C45") (pin "1") (pinfunction "1_1") (pintype "passive"))
      (node (ref "C46") (pin "1") (pinfunction "1_1") (pintype "passive"))
      (node (ref "C47") (pin "1") (pinfunction "1_1") (pintype "passive"))
      (node (ref "C48") (pin "1") (pinfunction "1_1") (pintype "passive"))
      (node (ref "C49") (pin "1") (pinfunction "1_1") (pintype "passive"))
      (node (ref "C5") (pin "2") (pinfunction "2_2") (pintype "passive"))
      (node (ref "C50") (pin "2") (pinfunction "2_2") (pintype "passive"))
      (node (ref "C51") (pin "2") (pinfunction "2_2") (pintype "passive"))
      (node (ref "C52") (pin "2") (pinfunction "2_2") (pintype "passive"))
      (node (ref "C53") (pin "2") (pinfunction "2_2") (pintype "passive"))
      (node (ref "C54") (pin "2") (pinfunction "2_2") (pintype "passive"))
      (node (ref "C7") (pin "1") (pinfunction "1_1") (pintype "passive"))
      (node (ref "C8") (pin "2") (pinfunction "2_2") (pintype "passive"))
      (node (ref "C9") (pin "2") (pinfunction "2_2") (pintype "passive"))
      (node (ref "D1") (pin "1") (pinfunction "A_1") (pintype "passive"))
      (node (ref "D7") (pin "1") (pinfunction "A_1") (pintype "passive"))
      (node (ref "D8") (pin "2") (pinfunction "K_2") (pintype "passive"))
      (node (ref "D9") (pin "K") (pinfunction "K_K") (pintype "passive"))
      (node (ref "L2") (pin "2") (pinfunction "2_2") (pintype "passive"))
      (node (ref "L3") (pin "1") (pinfunction "1_1") (pintype "passive"))
      (node (ref "R27") (pin "1") (pinfunction "1_1") (pintype "passive"))
      (node (ref "RESET1") (pin "2") (pinfunction "2_2") (pintype "passive"))
      (node (ref "RS1") (pin "4") (pinfunction "4_4") (pintype "passive"))
      (node (ref "RS2") (pin "3") (pinfunction "3_3") (pintype "passive"))
      (node (ref "S1") (pin "2") (pinfunction "2_2") (pintype "passive"))
      (node (ref "SWD1") (pin "3") (pinfunction "3_3") (pintype "passive"))
      (node (ref "U1") (pin "15") (pinfunction "GND_15") (pintype "power_in"))
      (node (ref "U10") (pin "2") (pinfunction "GND_2") (pintype "passive"))
      (node (ref "U10") (pin "8") (pinfunction "S_8") (pintype "passive"))
      (node (ref "U2") (pin "5") (pinfunction "GND_5") (pintype "power_in"))
      (node (ref "U3") (pin "3") (pinfunction "GND_3") (pintype "power_in"))
      (node (ref "U3") (pin "5") (pinfunction "~{ON}/OFF_5") (pintype "input"))
      (node (ref "U3") (pin "6") (pinfunction "6_6") (pintype "power_in"))
      (node (ref "U4") (pin "4") (pinfunction "FB_4") (pintype "input"))
      (node (ref "U5") (pin "12") (pinfunction "VSSA_12") (pintype "power_in"))
      (node (ref "U5") (pin "18") (pinfunction "VSS_18") (pintype "power_in"))
      (node (ref "U5") (pin "63") (pinfunction "VSS_63") (pintype "power_in"))
      (node (ref "U9") (pin "1") (pinfunction "GND_1") (pintype "passive"))
      (node (ref "USB_USART1") (pin "5") (pinfunction "VSS_5") (pintype "passive"))
      (node (ref "VR1") (pin "1") (pinfunction "GND_1") (pintype "passive"))
    )
    (net (code "51") (name "Net-(*3-E{slash}S#)") (class "Default")
      (node (ref "*3") (pin "4") (pinfunction "E/S#_4") (pintype "passive"))
      (node (ref "*3") (pin "7") (pinfunction "Vdig_7") (pintype "passive"))
      (node (ref "D5") (pin "2") (pinfunction "K_2") (pintype "passive"))
      (node (ref "R6") (pin "1") (pinfunction "1_1") (pintype "passive"))
    )
    (net (code "52") (name "Net-(*3-Iset)") (class "Default")
      (node (ref "*3") (pin "9") (pinfunction "Iset_9") (pintype "passive"))
      (node (ref "C24") (pin "2") (pinfunction "2_2") (pintype "passive"))
      (node (ref "R10") (pin "2") (pinfunction "2_2") (pintype "passive"))
    )
    (net (code "53") (name "Net-(*4--IN)") (class "Default")
      (node (ref "*4") (pin "15") (pinfunction "Vout_15") (pintype "passive"))
      (node (ref "*4") (pin "16") (pinfunction "Vout_16") (pintype "passive"))
      (node (ref "*4") (pin "6") (pinfunction "-IN_6") (pintype "passive"))
      (node (ref "R7") (pin "1") (pinfunction "1_1") (pintype "passive"))
      (node (ref "U7") (pin "3") (pinfunction "+IN_3") (pintype "input"))
    )
    (net (code "54") (name "Net-(*4-E{slash}S#)") (class "Default")
      (node (ref "*4") (pin "4") (pinfunction "E/S#_4") (pintype "passive"))
      (node (ref "*4") (pin "7") (pinfunction "Vdig_7") (pintype "passive"))
      (node (ref "D6") (pin "2") (pinfunction "K_2") (pintype "passive"))
      (node (ref "R8") (pin "1") (pinfunction "1_1") (pintype "passive"))
    )
    (net (code "55") (name "Net-(*4-Iset)") (class "Default")
      (node (ref "*4") (pin "9") (pinfunction "Iset_9") (pintype "passive"))
      (node (ref "C25") (pin "2") (pinfunction "2_2") (pintype "passive"))
      (node (ref "R11") (pin "2") (pinfunction "2_2") (pintype "passive"))
    )
    (net (code "56") (name "Net-(*6-V+)") (class "Default")
      (node (ref "*6") (pin "2") (pinfunction "V+_2") (pintype "passive"))
      (node (ref "C30") (pin "2") (pinfunction "2_2") (pintype "passive"))
      (node (ref "R18") (pin "1") (pinfunction "1_1") (pintype "passive"))
      (node (ref "U7") (pin "5") (pinfunction "REF_5") (pintype "input"))
    )
    (net (code "57") (name "Net-(*7-V+)") (class "Default")
      (node (ref "*7") (pin "2") (pinfunction "V+_2") (pintype "passive"))
      (node (ref "C31") (pin "2") (pinfunction "2_2") (pintype "passive"))
      (node (ref "R19") (pin "1") (pinfunction "1_1") (pintype "passive"))
      (node (ref "U8") (pin "5") (pinfunction "REF_5") (pintype "input"))
    )
    (net (code "58") (name "Net-(*8-V+)") (class "Default")
      (node (ref "*8") (pin "2") (pinfunction "V+_2") (pintype "passive"))
      (node (ref "C32") (pin "2") (pinfunction "2_2") (pintype "passive"))
      (node (ref "R20") (pin "1") (pinfunction "1_1") (pintype "passive"))
      (node (ref "U6") (pin "5") (pinfunction "REF_5") (pintype "input"))
    )
    (net (code "59") (name "Net-(D1-K)") (class "Default")
      (node (ref "D1") (pin "2") (pinfunction "K_2") (pintype "passive"))
      (node (ref "L1") (pin "1") (pinfunction "1_1") (pintype "passive"))
      (node (ref "U3") (pin "2") (pinfunction "OUT_2") (pintype "power_in"))
    )
    (net (code "60") (name "Net-(D2-PadA)") (class "Default")
      (node (ref "D2") (pin "A") (pinfunction "A_A") (pintype "passive"))
      (node (ref "R3") (pin "2") (pinfunction "2_2") (pintype "passive"))
    )
    (net (code "61") (name "Net-(D3-PadA)") (class "Default")
      (node (ref "D3") (pin "A") (pinfunction "A_A") (pintype "passive"))
      (node (ref "R4") (pin "2") (pinfunction "2_2") (pintype "passive"))
    )
    (net (code "62") (name "Net-(D4-K)") (class "Default")
      (node (ref "D4") (pin "2") (pinfunction "K_2") (pintype "passive"))
      (node (ref "L2") (pin "1") (pinfunction "1_1") (pintype "passive"))
      (node (ref "U4") (pin "2") (pinfunction "OUT_2") (pintype "power_in"))
    )
    (net (code "63") (name "Net-(D9-PadA)") (class "Default")
      (node (ref "D9") (pin "A") (pinfunction "A_A") (pintype "passive"))
      (node (ref "R24") (pin "2") (pinfunction "2_2") (pintype "passive"))
    )
    (net (code "64") (name "Net-(R13-Pad1)") (class "Default")
      (node (ref "R13") (pin "1") (pinfunction "1_1") (pintype "passive"))
      (node (ref "U8") (pin "1") (pinfunction "RG_1") (pintype "passive"))
    )
    (net (code "65") (name "Net-(R13-Pad2)") (class "Default")
      (node (ref "R13") (pin "2") (pinfunction "2_2") (pintype "passive"))
      (node (ref "U8") (pin "8") (pinfunction "RG_8") (pintype "passive"))
    )
    (net (code "66") (name "Net-(R14-Pad1)") (class "Default")
      (node (ref "R14") (pin "1") (pinfunction "1_1") (pintype "passive"))
      (node (ref "U7") (pin "1") (pinfunction "RG_1") (pintype "passive"))
    )
    (net (code "67") (name "Net-(R14-Pad2)") (class "Default")
      (node (ref "R14") (pin "2") (pinfunction "2_2") (pintype "passive"))
      (node (ref "U7") (pin "8") (pinfunction "RG_8") (pintype "passive"))
    )
    (net (code "68") (name "Net-(R15-Pad1)") (class "Default")
      (node (ref "R15") (pin "1") (pinfunction "1_1") (pintype "passive"))
      (node (ref "U6") (pin "1") (pinfunction "RG_1") (pintype "passive"))
    )
    (net (code "69") (name "Net-(R15-Pad2)") (class "Default")
      (node (ref "R15") (pin "2") (pinfunction "2_2") (pintype "passive"))
      (node (ref "U6") (pin "8") (pinfunction "RG_8") (pintype "passive"))
    )
    (net (code "70") (name "Net-(U1-C1+)") (class "Default")
      (node (ref "C2") (pin "2") (pinfunction "2_2") (pintype "passive"))
      (node (ref "U1") (pin "1") (pinfunction "C1+_1") (pintype "passive"))
    )
    (net (code "71") (name "Net-(U1-C1-)") (class "Default")
      (node (ref "C2") (pin "1") (pinfunction "1_1") (pintype "passive"))
      (node (ref "U1") (pin "3") (pinfunction "C1-_3") (pintype "passive"))
    )
    (net (code "72") (name "Net-(U1-C2+)") (class "Default")
      (node (ref "C4") (pin "1") (pinfunction "1_1") (pintype "passive"))
      (node (ref "U1") (pin "4") (pinfunction "C2+_4") (pintype "passive"))
    )
    (net (code "73") (name "Net-(U1-C2-)") (class "Default")
      (node (ref "C4") (pin "2") (pinfunction "2_2") (pintype "passive"))
      (node (ref "U1") (pin "5") (pinfunction "C2-_5") (pintype "passive"))
    )
    (net (code "74") (name "Net-(U1-V+)") (class "Default")
      (node (ref "C5") (pin "1") (pinfunction "1_1") (pintype "passive"))
      (node (ref "U1") (pin "2") (pinfunction "V+_2") (pintype "power_in"))
    )
    (net (code "75") (name "Net-(U1-V-)") (class "Default")
      (node (ref "C8") (pin "1") (pinfunction "1_1") (pintype "passive"))
      (node (ref "U1") (pin "6") (pinfunction "V-_6") (pintype "power_in"))
    )
    (net (code "76") (name "Net-(U5A-BOOT0)") (class "Default")
      (node (ref "R27") (pin "2") (pinfunction "2_2") (pintype "passive"))
      (node (ref "U5") (pin "60") (pinfunction "BOOT0_60") (pintype "input"))
    )
    (net (code "77") (name "Net-(U5A-VCAP_1)") (class "Default")
      (node (ref "C40") (pin "1") (pinfunction "1_1") (pintype "passive"))
      (node (ref "U5") (pin "31") (pinfunction "VCAP_1_31") (pintype "power_in"))
    )
    (net (code "78") (name "Net-(U5A-VCAP_2)") (class "Default")
      (node (ref "C41") (pin "1") (pinfunction "1_1") (pintype "passive"))
      (node (ref "U5") (pin "47") (pinfunction "VCAP_2_47") (pintype "power_in"))
    )
    (net (code "79") (name "Net-(U5B-VDDA)") (class "Default")
      (node (ref "C52") (pin "1") (pinfunction "1_1") (pintype "passive"))
      (node (ref "L4") (pin "1") (pinfunction "1_1") (pintype "passive"))
      (node (ref "U5") (pin "13") (pinfunction "VDDA_13") (pintype "power_in"))
    )
    (net (code "80") (name "Net-(U8-+IN)") (class "Default")
      (node (ref "R12") (pin "1") (pinfunction "1_1") (pintype "passive"))
      (node (ref "R9") (pin "2") (pinfunction "2_2") (pintype "passive"))
      (node (ref "U8") (pin "3") (pinfunction "+IN_3") (pintype "input"))
    )
    (net (code "81") (name "Net-(U9-V3.3)") (class "Default")
      (node (ref "C43") (pin "1") (pinfunction "1_1") (pintype "passive"))
      (node (ref "U9") (pin "4") (pinfunction "V3.3_4") (pintype "passive"))
    )
    (net (code "82") (name "Net-(U9-XI)") (class "Default")
      (node (ref "C45") (pin "2") (pinfunction "2_2") (pintype "passive"))
      (node (ref "U9") (pin "7") (pinfunction "XI_7") (pintype "passive"))
      (node (ref "Y1") (pin "1") (pinfunction "OSC1_1") (pintype "passive"))
    )
    (net (code "83") (name "Net-(U9-XO)") (class "Default")
      (node (ref "C46") (pin "2") (pinfunction "2_2") (pintype "passive"))
      (node (ref "U9") (pin "8") (pinfunction "XO_8") (pintype "passive"))
      (node (ref "Y1") (pin "3") (pinfunction "OSC2_3") (pintype "passive"))
    )
    (net (code "84") (name "SGND") (class "Default")
      (node (ref "*1") (pin "18") (pinfunction "DAC_GND_18") (pintype "passive"))
      (node (ref "*1") (pin "19") (pinfunction "DAC_GND_19") (pintype "passive"))
      (node (ref "*1") (pin "20") (pinfunction "SIG_GND_20") (pintype "passive"))
      (node (ref "*1") (pin "21") (pinfunction "SIG_GND_21") (pintype "passive"))
      (node (ref "*2") (pin "1") (pinfunction "V-_1") (pintype "passive"))
      (node (ref "*6") (pin "1") (pinfunction "V-_1") (pintype "passive"))
      (node (ref "*7") (pin "1") (pinfunction "V-_1") (pintype "passive"))
      (node (ref "*8") (pin "1") (pinfunction "V-_1") (pintype "passive"))
      (node (ref "*9") (pin "1") (pinfunction "ADDR_1") (pintype "passive"))
      (node (ref "*9") (pin "3") (pinfunction "GND_3") (pintype "passive"))
      (node (ref "*9") (pin "7") (pinfunction "AIN3_7") (pintype "passive"))
      (node (ref "C10") (pin "2") (pinfunction "2_2") (pintype "passive"))
      (node (ref "C11") (pin "1") (pinfunction "1_1") (pintype "passive"))
      (node (ref "C12") (pin "1") (pinfunction "1_1") (pintype "passive"))
      (node (ref "C13") (pin "1") (pinfunction "1_1") (pintype "passive"))
      (node (ref "C14") (pin "2") (pinfunction "2_2") (pintype "passive"))
      (node (ref "C15") (pin "1") (pinfunction "1_1") (pintype "passive"))
      (node (ref "C16") (pin "1") (pinfunction "1_1") (pintype "passive"))
      (node (ref "C17") (pin "1") (pinfunction "1_1") (pintype "passive"))
      (node (ref "C30") (pin "1") (pinfunction "1_1") (pintype "passive"))
      (node (ref "C31") (pin "1") (pinfunction "1_1") (pintype "passive"))
      (node (ref "C32") (pin "1") (pinfunction "1_1") (pintype "passive"))
      (node (ref "C33") (pin "1") (pinfunction "1_1") (pintype "passive"))
      (node (ref "C34") (pin "1") (pinfunction "1_1") (pintype "passive"))
      (node (ref "C35") (pin "1") (pinfunction "1_1") (pintype "passive"))
      (node (ref "C36") (pin "1") (pinfunction "1_1") (pintype "passive"))
      (node (ref "C37") (pin "1") (pinfunction "1_1") (pintype "passive"))
      (node (ref "C38") (pin "1") (pinfunction "1_1") (pintype "passive"))
      (node (ref "C44") (pin "2") (pinfunction "2_2") (pintype "passive"))
      (node (ref "C6") (pin "1") (pinfunction "1_1") (pintype "passive"))
      (node (ref "DA1") (pin "2") (pinfunction "2_2") (pintype "passive"))
      (node (ref "DA2") (pin "2") (pinfunction "2_2") (pintype "passive"))
      (node (ref "Force Sensor1") (pin "4") (pinfunction "4_4") (pintype "passive"))
      (node (ref "L3") (pin "2") (pinfunction "2_2") (pintype "passive"))
      (node (ref "R12") (pin "2") (pinfunction "2_2") (pintype "passive"))
      (node (ref "U8") (pin "2") (pinfunction "-IN_2") (pintype "input"))
    )
    (net (code "85") (name "unconnected-(*1-NC-Pad2)") (class "Default")
      (node (ref "*1") (pin "2") (pinfunction "NC_2") (pintype "passive"))
    )
    (net (code "86") (name "unconnected-(*1-NC-Pad4)") (class "Default")
      (node (ref "*1") (pin "4") (pinfunction "NC_4") (pintype "passive"))
    )
    (net (code "87") (name "unconnected-(*1-NC-Pad6)") (class "Default")
      (node (ref "*1") (pin "6") (pinfunction "NC_6") (pintype "passive"))
    )
    (net (code "88") (name "unconnected-(*1-NC-Pad12)") (class "Default")
      (node (ref "*1") (pin "12") (pinfunction "NC_12") (pintype "passive"))
    )
    (net (code "89") (name "unconnected-(*1-NC-Pad13)") (class "Default")
      (node (ref "*1") (pin "13") (pinfunction "NC_13") (pintype "passive"))
    )
    (net (code "90") (name "unconnected-(*1-NC-Pad22)") (class "Default")
      (node (ref "*1") (pin "22") (pinfunction "NC_22") (pintype "passive"))
    )
    (net (code "91") (name "unconnected-(*2-ADJ-Pad3)") (class "Default")
      (node (ref "*2") (pin "3") (pinfunction "ADJ_3") (pintype "passive"))
    )
    (net (code "92") (name "unconnected-(*3-Iflag-Pad8)") (class "Default")
      (node (ref "*3") (pin "8") (pinfunction "Iflag_8") (pintype "passive"))
    )
    (net (code "93") (name "unconnected-(*3-Tflag-Pad3)") (class "Default")
      (node (ref "*3") (pin "3") (pinfunction "Tflag_3") (pintype "passive"))
    )
    (net (code "94") (name "unconnected-(*3-Tsense-Pad12)") (class "Default")
      (node (ref "*3") (pin "12") (pinfunction "Tsense_12") (pintype "passive"))
    )
    (net (code "95") (name "unconnected-(*4-Iflag-Pad8)") (class "Default")
      (node (ref "*4") (pin "8") (pinfunction "Iflag_8") (pintype "passive"))
    )
    (net (code "96") (name "unconnected-(*4-Tflag-Pad3)") (class "Default")
      (node (ref "*4") (pin "3") (pinfunction "Tflag_3") (pintype "passive"))
    )
    (net (code "97") (name "unconnected-(*4-Tsense-Pad12)") (class "Default")
      (node (ref "*4") (pin "12") (pinfunction "Tsense_12") (pintype "passive"))
    )
    (net (code "98") (name "unconnected-(*6-ADJ-Pad3)") (class "Default")
      (node (ref "*6") (pin "3") (pinfunction "ADJ_3") (pintype "passive"))
    )
    (net (code "99") (name "unconnected-(*7-ADJ-Pad3)") (class "Default")
      (node (ref "*7") (pin "3") (pinfunction "ADJ_3") (pintype "passive"))
    )
    (net (code "100") (name "unconnected-(*8-ADJ-Pad3)") (class "Default")
      (node (ref "*8") (pin "3") (pinfunction "ADJ_3") (pintype "passive"))
    )
    (net (code "101") (name "unconnected-(*10-NC-Pad3)") (class "Default")
      (node (ref "*10") (pin "3") (pinfunction "NC_3") (pintype "passive"))
    )
    (net (code "102") (name "unconnected-(*10-NC-Pad4)") (class "Default")
      (node (ref "*10") (pin "4") (pinfunction "NC_4") (pintype "passive"))
    )
    (net (code "103") (name "unconnected-(RS1-Pad1)") (class "Default")
      (node (ref "RS1") (pin "1") (pinfunction "1_1") (pintype "passive"))
    )
    (net (code "104") (name "unconnected-(RS1-Pad2)") (class "Default")
      (node (ref "RS1") (pin "2") (pinfunction "2_2") (pintype "passive"))
    )
    (net (code "105") (name "unconnected-(RS1-Pad6)") (class "Default")
      (node (ref "RS1") (pin "6") (pinfunction "6_6") (pintype "passive"))
    )
    (net (code "106") (name "unconnected-(T1-Pad1)") (class "Default")
      (node (ref "T1") (pin "1") (pinfunction "1_1") (pintype "passive"))
    )
    (net (code "107") (name "unconnected-(T2-Pad1)") (class "Default")
      (node (ref "T2") (pin "1") (pinfunction "1_1") (pintype "passive"))
    )
    (net (code "108") (name "unconnected-(T3-Pad1)") (class "Default")
      (node (ref "T3") (pin "1") (pinfunction "1_1") (pintype "passive"))
    )
    (net (code "109") (name "unconnected-(T4-Pad1)") (class "Default")
      (node (ref "T4") (pin "1") (pinfunction "1_1") (pintype "passive"))
    )
    (net (code "110") (name "unconnected-(U1-R2IN-Pad8)") (class "Default")
      (node (ref "U1") (pin "8") (pinfunction "R2IN_8") (pintype "input+no_connect"))
    )
    (net (code "111") (name "unconnected-(U1-R2OUT-Pad9)") (class "Default")
      (node (ref "U1") (pin "9") (pinfunction "R2OUT_9") (pintype "output"))
    )
    (net (code "112") (name "unconnected-(U1-T2IN-Pad10)") (class "Default")
      (node (ref "U1") (pin "10") (pinfunction "T2IN_10") (pintype "input+no_connect"))
    )
    (net (code "113") (name "unconnected-(U1-T2OUT-Pad7)") (class "Default")
      (node (ref "U1") (pin "7") (pinfunction "T2OUT_7") (pintype "output"))
    )
    (net (code "114") (name "unconnected-(U5A-PA0-WKUP(PA0)-Pad14)") (class "Default")
      (node (ref "U5") (pin "14") (pinfunction "PA0-WKUP(PA0)_14") (pintype "bidirectional"))
    )
    (net (code "115") (name "unconnected-(U5A-PA1-Pad15)") (class "Default")
      (node (ref "U5") (pin "15") (pinfunction "PA1_15") (pintype "bidirectional"))
    )
    (net (code "116") (name "unconnected-(U5A-PA4-Pad20)") (class "Default")
      (node (ref "U5") (pin "20") (pinfunction "PA4_20") (pintype "bidirectional"))
    )
    (net (code "117") (name "unconnected-(U5A-PA5-Pad21)") (class "Default")
      (node (ref "U5") (pin "21") (pinfunction "PA5_21") (pintype "bidirectional"))
    )
    (net (code "118") (name "unconnected-(U5A-PA6-Pad22)") (class "Default")
      (node (ref "U5") (pin "22") (pinfunction "PA6_22") (pintype "bidirectional"))
    )
    (net (code "119") (name "unconnected-(U5A-PA7-Pad23)") (class "Default")
      (node (ref "U5") (pin "23") (pinfunction "PA7_23") (pintype "bidirectional"))
    )
    (net (code "120") (name "unconnected-(U5A-PA8-Pad41)") (class "Default")
      (node (ref "U5") (pin "41") (pinfunction "PA8_41") (pintype "bidirectional"))
    )
    (net (code "121") (name "unconnected-(U5A-PA15(JTDI)-Pad50)") (class "Default")
      (node (ref "U5") (pin "50") (pinfunction "PA15(JTDI)_50") (pintype "bidirectional"))
    )
    (net (code "122") (name "unconnected-(U5A-PB0-Pad26)") (class "Default")
      (node (ref "U5") (pin "26") (pinfunction "PB0_26") (pintype "bidirectional"))
    )
    (net (code "123") (name "unconnected-(U5A-PB1-Pad27)") (class "Default")
      (node (ref "U5") (pin "27") (pinfunction "PB1_27") (pintype "bidirectional"))
    )
    (net (code "124") (name "unconnected-(U5A-PB2-BOOT1(PB2)-Pad28)") (class "Default")
      (node (ref "U5") (pin "28") (pinfunction "PB2-BOOT1(PB2)_28") (pintype "bidirectional"))
    )
    (net (code "125") (name "unconnected-(U5A-PB3(JTDO{slash}TRACESWO)-Pad55)") (class "Default")
      (node (ref "U5") (pin "55") (pinfunction "PB3(JTDO/TRACESWO)_55") (pintype "bidirectional"))
    )
    (net (code "126") (name "unconnected-(U5A-PB4(NJTRST)-Pad56)") (class "Default")
      (node (ref "U5") (pin "56") (pinfunction "PB4(NJTRST)_56") (pintype "bidirectional"))
    )
    (net (code "127") (name "unconnected-(U5A-PB8-Pad61)") (class "Default")
      (node (ref "U5") (pin "61") (pinfunction "PB8_61") (pintype "bidirectional"))
    )
    (net (code "128") (name "unconnected-(U5A-PB9-Pad62)") (class "Default")
      (node (ref "U5") (pin "62") (pinfunction "PB9_62") (pintype "bidirectional"))
    )
    (net (code "129") (name "unconnected-(U5A-PC3-Pad11)") (class "Default")
      (node (ref "U5") (pin "11") (pinfunction "PC3_11") (pintype "bidirectional"))
    )
    (net (code "130") (name "unconnected-(U5A-PC4-Pad24)") (class "Default")
      (node (ref "U5") (pin "24") (pinfunction "PC4_24") (pintype "bidirectional"))
    )
    (net (code "131") (name "unconnected-(U5A-PC5-Pad25)") (class "Default")
      (node (ref "U5") (pin "25") (pinfunction "PC5_25") (pintype "bidirectional"))
    )
    (net (code "132") (name "unconnected-(U5A-PC6-Pad37)") (class "Default")
      (node (ref "U5") (pin "37") (pinfunction "PC6_37") (pintype "bidirectional"))
    )
    (net (code "133") (name "unconnected-(U5A-PC7-Pad38)") (class "Default")
      (node (ref "U5") (pin "38") (pinfunction "PC7_38") (pintype "bidirectional"))
    )
    (net (code "134") (name "unconnected-(U5A-PC8-Pad39)") (class "Default")
      (node (ref "U5") (pin "39") (pinfunction "PC8_39") (pintype "bidirectional"))
    )
    (net (code "135") (name "unconnected-(U5A-PC9-Pad40)") (class "Default")
      (node (ref "U5") (pin "40") (pinfunction "PC9_40") (pintype "bidirectional"))
    )
    (net (code "136") (name "unconnected-(U5A-PC13-Pad2)") (class "Default")
      (node (ref "U5") (pin "2") (pinfunction "PC13_2") (pintype "bidirectional"))
    )
    (net (code "137") (name "unconnected-(U5A-PC14-OSC32_IN(PC14)-Pad3)") (class "Default")
      (node (ref "U5") (pin "3") (pinfunction "PC14-OSC32_IN(PC14)_3") (pintype "bidirectional"))
    )
    (net (code "138") (name "unconnected-(U5A-PC15-OSC32_OUT(PC15)-Pad4)") (class "Default")
      (node (ref "U5") (pin "4") (pinfunction "PC15-OSC32_OUT(PC15)_4") (pintype "bidirectional"))
    )
    (net (code "139") (name "unconnected-(U5A-PD2-Pad54)") (class "Default")
      (node (ref "U5") (pin "54") (pinfunction "PD2_54") (pintype "bidirectional"))
    )
    (net (code "140") (name "unconnected-(U9-CTS#-Pad9)") (class "Default")
      (node (ref "U9") (pin "9") (pinfunction "CTS#_9") (pintype "passive"))
    )
    (net (code "141") (name "unconnected-(U9-DCD#-Pad13)") (class "Default")
      (node (ref "U9") (pin "13") (pinfunction "DCD#_13") (pintype "passive"))
    )
    (net (code "142") (name "unconnected-(U9-DSR#-Pad10)") (class "Default")
      (node (ref "U9") (pin "10") (pinfunction "DSR#_10") (pintype "passive"))
    )
    (net (code "143") (name "unconnected-(U9-DTR#-Pad12)") (class "Default")
      (node (ref "U9") (pin "12") (pinfunction "DTR#_12") (pintype "passive"))
    )
    (net (code "144") (name "unconnected-(U9-R232-Pad15)") (class "Default")
      (node (ref "U9") (pin "15") (pinfunction "R232_15") (pintype "passive"))
    )
    (net (code "145") (name "unconnected-(U9-RI#-Pad14)") (class "Default")
      (node (ref "U9") (pin "14") (pinfunction "RI#_14") (pintype "passive"))
    )
    (net (code "146") (name "unconnected-(U9-RTS#-Pad11)") (class "Default")
      (node (ref "U9") (pin "11") (pinfunction "RTS#_11") (pintype "passive"))
    )
    (net (code "147") (name "unconnected-(U10-n.c.-Pad5)") (class "Default")
      (node (ref "U10") (pin "5") (pinfunction "n.c._5") (pintype "passive"))
    )
    (net (code "148") (name "unconnected-(USB_USART1-ID-Pad4)") (class "Default")
      (node (ref "USB_USART1") (pin "4") (pinfunction "ID_4") (pintype "passive"))
    )
  )
)
